# smarttrashcan.net
KiCad netlist of a schematic drawn in Altium Designer
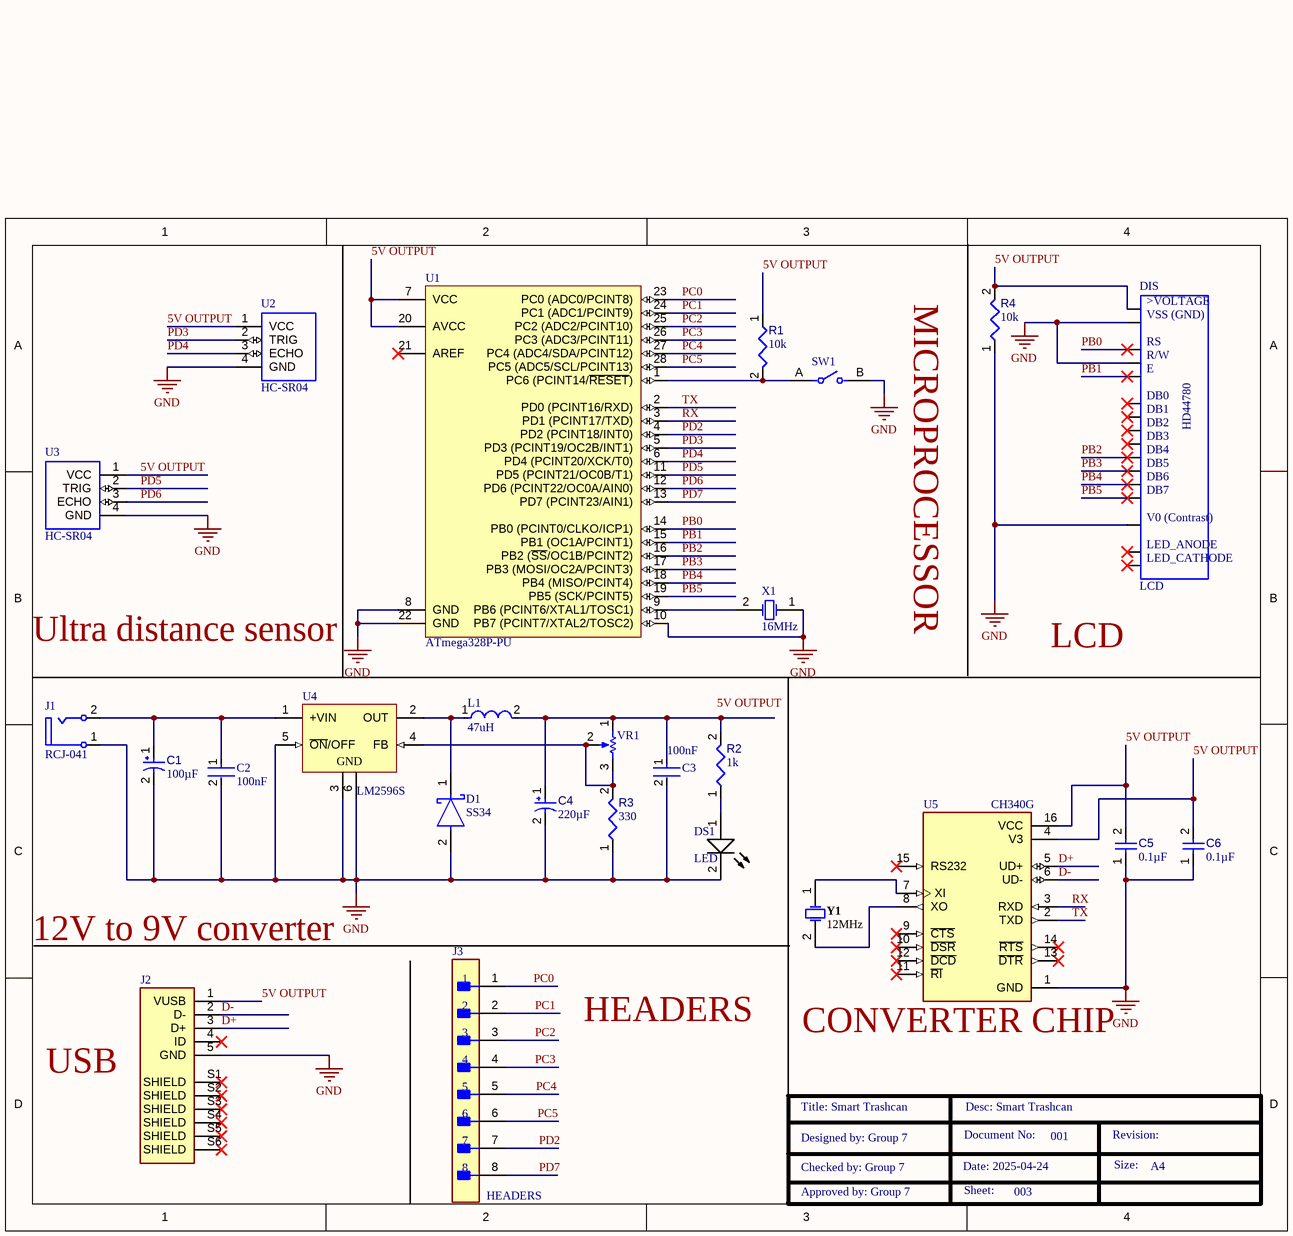
[diagram p0: smarttrashcan.SchDoc]

(export (version "E")
  (design (tool "Eeschema 10.0.6"))
  (components
    (comp (ref "C1")
      (value "100µF")
      (footprint "CAPPR65-500-1600X1000X1700")
      (description "Aluminum Electrolytic Capacitor, 100 uF, +/- 20%, 100 V, -40 to 85 degC, 2-Pin THD, RoHS, Bulk")
      (fields (field (name "MANUFACTURER") "Panasonic") (field (name "TOLERANCE") "20%"))
      (libsource (lib "Uy Pham") (part "CAP-P-2"))
    )
    (comp (ref "C2")
      (value "100nF")
      (footprint "FP-1812-L_4_5_0_3-W_3_2_0-IPC_C")
      (description "General Purpose Ceramic Capacitor, 1812, 100nF, 10%, X7R, 15%, 100V")
      (fields (field (name "TOLERANCE") "10%") (field (name "VOLTAGE") "100V"))
      (libsource (lib "Altium Content Vault") (part "02cd4be3c70576c341d710602a673aa"))
    )
    (comp (ref "C3")
      (value "100nF")
      (footprint "FP-1812-L_4_5_0_3-W_3_2_0-IPC_C")
      (description "General Purpose Ceramic Capacitor, 1812, 100nF, 10%, X7R, 15%, 100V")
      (fields (field (name "TOLERANCE") "10%") (field (name "VOLTAGE") "100V"))
      (libsource (lib "Altium Content Vault") (part "02cd4be3c70576c341d710602a673aa"))
    )
    (comp (ref "C4")
      (value "220µF")
      (footprint "CAPMP7344X31-T_V")
      (fields
        (field (name "TOLERANCE") "10%")
        (field (name "MANUFACTURER") "AVX Corporation")
        (field (name "Comment") "TPSD227K010R0150")
      )
      (libsource (lib "Uy Pham") (part "CAP-P-2"))
    )
    (comp (ref "C5")
      (value "0.1µF")
      (footprint "CAPC1005X56X25LL10T15")
      (description "Chip Capacitor, 0.1 uF, +/- 5%, 16 V, 0402 (1005 Metric)")
      (fields (field (name "TOLERANCE") "5%") (field (name "Comment") "Capacitor 0.1 uF +/- 5% 16 V 0402"))
      (libsource (lib "Uy Pham") (part "CAP-NP-2"))
    )
    (comp (ref "C6")
      (value "0.1µF")
      (footprint "CAPC1005X56X25LL10T15")
      (description "Chip Capacitor, 0.1 uF, +/- 5%, 16 V, 0402 (1005 Metric)")
      (fields (field (name "TOLERANCE") "5%") (field (name "Comment") "Capacitor 0.1 uF +/- 5% 16 V 0402"))
      (libsource (lib "Uy Pham") (part "CAP-NP-2"))
    )
    (comp (ref "D1")
      (value "SS34")
      (footprint "FP-95402-MFG")
      (description "DIODE SCHOTTKY 40V 3A DO214AB")
      (fields (field (name "MANUFACTURER") "Vishay") (field (name "MANUFACTURER PART NUMBER") "SS34-E3/57T"))
      (libsource (lib "Altium Content Vault") (part "1d6ec82d83fb6aee721767c19dac4b9"))
    )
    (comp (ref "DIS")
      (value "LCD")
      (footprint "16026-16X2")
      (fields (field (name "MP") "HD44780") (field (name "MF") "Lumex Opto/Components"))
      (libsource (lib "Uy Pham") (part "HD44780"))
    )
    (comp (ref "DS1")
      (value "LED")
      (footprint "EVRL-0402-2_V")
      (description "Chip LED, White, 5 V, 10 mA, 30 mW, -40 to 85 degC, 2-Pin SMD (0402), RoHS, Tape and Reel")
      (fields (field (name "POWER") "30mW") (field (name "MANUFACTURER") "Everlight Electronics"))
      (libsource (lib "Uy Pham") (part "LED-WHITE-AK-2"))
    )
    (comp (ref "J1")
      (value "RCJ-041")
      (footprint "CUI-RCJ-041_V")
      (description "Female RCJ Jack, 2 Position, Height 11.724 mm, Tail Length 4 mm, RoHS, Bulk")
      (fields (field (name "MANUFACTURER") "CUI Inc"))
      (libsource (lib "Uy Pham") (part "JACK-2CD2"))
    )
    (comp (ref "J2")
      (value "10118193-0001LF")
      (footprint "AMPHENOL_10118193-0001LF")
      (description "Right Angle Surface Mount Mount Female USB Connector 100 V ac 1.8A")
      (fields (field (name "MF") "Amphenol ICC"))
      (libsource (lib "Uy Pham") (part "10118193-0001LF"))
    )
    (comp (ref "J3")
      (value "HEADERS")
      (footprint "FP-22-11-2082-MFG")
      (description "CONN HEADER VERT 8POS 2.54MM")
      (libsource (lib "Altium Content Vault") (part "99ec2b232beb5d2356d4d77f6a047f0"))
    )
    (comp (ref "L1")
      (value "47uH")
      (footprint "FP-LB3225-2_5-0_2-IPC_B")
      (description "Commercial Inductors, Low DCR Series 47uH 3.3A 145mΩ 20%")
      (fields (field (name "TOLERANCE") "20%"))
      (libsource (lib "Altium Content Vault") (part "725321dda6339637d4d059423bc1c3c"))
    )
    (comp (ref "R1")
      (value "10k")
      (footprint "RESC0402(1005)_L")
      (description "10K 0.063W 1% 0402 (1005 Metric)  SMD")
      (fields (field (name "POWER") "63mW") (field (name "TOLERANCE") "1%"))
      (libsource (lib "Uy Pham") (part "10KR2F"))
    )
    (comp (ref "R2")
      (value "1k")
      (footprint "RESC0402(1005)_L")
      (description "1K 0.063W 5% 0402 (1005 Metric)  SMD")
      (fields (field (name "POWER") "63mW") (field (name "TOLERANCE") "5%"))
      (libsource (lib "Uy Pham") (part "1KR2J"))
    )
    (comp (ref "R3")
      (value "330")
      (footprint "RESC0402(1005)_L")
      (description "330R 0.063W 5% 0402 (1005 Metric)  SMD")
      (fields (field (name "TOLERANCE") "5%") (field (name "POWER") "63mW"))
      (libsource (lib "Uy Pham") (part "330R2J"))
    )
    (comp (ref "R4")
      (value "10k")
      (footprint "RESC0402(1005)_L")
      (description "10K 0.063W 1% 0402 (1005 Metric)  SMD")
      (fields (field (name "POWER") "63mW") (field (name "TOLERANCE") "1%"))
      (libsource (lib "Uy Pham") (part "10KR2F"))
    )
    (comp (ref "SW1")
      (value "EVQ11Y04K")
      (footprint "FP-EVQ11Y04K-MFG")
      (description "SWITCH TACTILE SPST-NO 0.02A 15V")
      (libsource (lib "Altium Content Vault") (part "2b0b2b19372efd94fa7681498149756"))
    )
    (comp (ref "U1")
      (value "ATmega328P-PU")
      (footprint "28P3")
      (libsource (lib "Altium Content Vault") (part "MC-8B-ATM48-IL28"))
    )
    (comp (ref "U2")
      (value "HC-SR04")
      (footprint "XCVR_HC-SR04")
      (description "Ultrasonic Sensor Module")
      (libsource (lib "Uy Pham") (part "HC-SR04"))
    )
    (comp (ref "U3")
      (value "HC-SR04")
      (footprint "XCVR_HC-SR04")
      (description "Ultrasonic Sensor Module")
      (libsource (lib "Uy Pham") (part "HC-SR04"))
    )
    (comp (ref "U4")
      (value "LM2596S")
      (footprint "KTT0005B_L")
      (fields (field (name "PARTNUMBER") "LM2596") (field (name "MANUFACTURER") "Texas Instruments"))
      (libsource (lib "Altium Content Vault") (part "TI-LM2596-TO-263-5"))
    )
    (comp (ref "U5")
      (value "CH340G")
      (footprint "SOIC127P600X180-16N")
      (description "USB Interface Integrated Circuit")
      (fields (field (name "MF") "WCH") (field (name "MP") "Ch340G"))
      (libsource (lib "Uy Pham") (part "CH340G"))
    )
    (comp (ref "VR1")
      (value "3296W-1-103LF")
      (footprint "BOUR-3296W")
      (fields
        (field (name "TOLERANCE") "10%")
        (field (name "POWER") "500mW")
        (field (name "MANUFACTURER") "Bourns")
      )
      (libsource (lib "Uy Pham") (part "RES-POT-3"))
    )
    (comp (ref "X1")
      (value "16MHz")
      (footprint "FOX-FOXSDLF160-20_V")
      (fields (field (name "TOLERANCE") "50ppm") (field (name "MANUFACTURER") "FOX Electronics"))
      (libsource (lib "Uy Pham") (part "XTAL_1-2-2"))
    )
    (comp (ref "Y1")
      (value "12MHz")
      (footprint "FOX-FOXSLF-2_V")
      (description "Resistance Weld Thru-Hole Crystal, 12 MHz, +/-30 ppm, 20 pF, -20 to 70 degC, 2-Pin THD, RoHS, Bulk")
      (fields (field (name "MANUFACTURER") "FOX Electronics") (field (name "TOLERANCE") "50ppm"))
      (libsource (lib "Uy Pham") (part "XTAL-1-2-2"))
    )
  )
  (nets
    (net (code "1") (name "/5V OUTPUT") (class "Default")
      (node (ref "C5") (pin "2") (pinfunction "2_2") (pintype "passive"))
      (node (ref "C6") (pin "2") (pinfunction "2_2") (pintype "passive"))
      (node (ref "DIS") (pin "P$2") (pinfunction "VDD_P$2") (pintype "bidirectional"))
      (node (ref "J2") (pin "1") (pinfunction "VUSB_1") (pintype "passive"))
      (node (ref "R1") (pin "1") (pinfunction "1_1") (pintype "passive"))
      (node (ref "R4") (pin "2") (pinfunction "2_2") (pintype "passive"))
      (node (ref "U1") (pin "20") (pinfunction "AVCC_20") (pintype "power_in"))
      (node (ref "U1") (pin "7") (pinfunction "VCC_7") (pintype "power_in"))
      (node (ref "U2") (pin "1") (pinfunction "VCC_1") (pintype "power_in"))
      (node (ref "U3") (pin "1") (pinfunction "VCC_1") (pintype "power_in"))
      (node (ref "U5") (pin "16") (pinfunction "VCC_16") (pintype "power_in"))
      (node (ref "U5") (pin "4") (pinfunction "V3_4") (pintype "power_in"))
    )
    (net (code "2") (name "/D+") (class "Default")
      (node (ref "J2") (pin "3") (pinfunction "D+_3") (pintype "passive"))
      (node (ref "U5") (pin "5") (pinfunction "UD+_5") (pintype "bidirectional"))
    )
    (net (code "3") (name "/D-") (class "Default")
      (node (ref "J2") (pin "2") (pinfunction "D-_2") (pintype "passive"))
      (node (ref "U5") (pin "6") (pinfunction "UD-_6") (pintype "bidirectional"))
    )
    (net (code "4") (name "/PB0") (class "Default")
      (node (ref "DIS") (pin "P$4") (pinfunction "RS_P$4") (pintype "bidirectional"))
      (node (ref "U1") (pin "14") (pinfunction "PB0_(PCINT0/CLKO/ICP1)_14") (pintype "bidirectional"))
    )
    (net (code "5") (name "/PB1") (class "Default")
      (node (ref "DIS") (pin "P$6") (pinfunction "E_P$6") (pintype "bidirectional"))
      (node (ref "U1") (pin "15") (pinfunction "PB1_(OC1A/PCINT1)_15") (pintype "bidirectional"))
    )
    (net (code "6") (name "/PB2") (class "Default")
      (node (ref "DIS") (pin "P$11") (pinfunction "DB4_P$11") (pintype "bidirectional"))
      (node (ref "U1") (pin "16") (pinfunction "PB2_(~{SS}/OC1B/PCINT2)_16") (pintype "bidirectional"))
    )
    (net (code "7") (name "/PB3") (class "Default")
      (node (ref "DIS") (pin "P$12") (pinfunction "DB5_P$12") (pintype "bidirectional"))
      (node (ref "U1") (pin "17") (pinfunction "PB3_(MOSI/OC2A/PCINT3)_17") (pintype "bidirectional"))
    )
    (net (code "8") (name "/PB4") (class "Default")
      (node (ref "DIS") (pin "P$13") (pinfunction "DB6_P$13") (pintype "bidirectional"))
      (node (ref "U1") (pin "18") (pinfunction "PB4_(MISO/PCINT4)_18") (pintype "bidirectional"))
    )
    (net (code "9") (name "/PB5") (class "Default")
      (node (ref "DIS") (pin "P$14") (pinfunction "DB7_P$14") (pintype "bidirectional"))
      (node (ref "U1") (pin "19") (pinfunction "PB5_(SCK/PCINT5)_19") (pintype "bidirectional"))
    )
    (net (code "10") (name "/PC0") (class "Default")
      (node (ref "J3") (pin "1") (pinfunction "1_1") (pintype "passive"))
      (node (ref "U1") (pin "23") (pinfunction "PC0_(ADC0/PCINT8)_23") (pintype "bidirectional"))
    )
    (net (code "11") (name "/PC1") (class "Default")
      (node (ref "J3") (pin "2") (pinfunction "2_2") (pintype "passive"))
      (node (ref "U1") (pin "24") (pinfunction "PC1_(ADC1/PCINT9)_24") (pintype "bidirectional"))
    )
    (net (code "12") (name "/PC2") (class "Default")
      (node (ref "J3") (pin "3") (pinfunction "3_3") (pintype "passive"))
      (node (ref "U1") (pin "25") (pinfunction "PC2_(ADC2/PCINT10)_25") (pintype "bidirectional"))
    )
    (net (code "13") (name "/PC3") (class "Default")
      (node (ref "J3") (pin "4") (pinfunction "4_4") (pintype "passive"))
      (node (ref "U1") (pin "26") (pinfunction "PC3_(ADC3/PCINT11)_26") (pintype "bidirectional"))
    )
    (net (code "14") (name "/PC4") (class "Default")
      (node (ref "J3") (pin "5") (pinfunction "5_5") (pintype "passive"))
      (node (ref "U1") (pin "27") (pinfunction "PC4_(ADC4/SDA/PCINT12)_27") (pintype "bidirectional"))
    )
    (net (code "15") (name "/PC5") (class "Default")
      (node (ref "J3") (pin "6") (pinfunction "6_6") (pintype "passive"))
      (node (ref "U1") (pin "28") (pinfunction "PC5_(ADC5/SCL/PCINT13)_28") (pintype "bidirectional"))
    )
    (net (code "16") (name "/PD2") (class "Default")
      (node (ref "J3") (pin "7") (pinfunction "7_7") (pintype "passive"))
      (node (ref "U1") (pin "4") (pinfunction "PD2_(PCINT18/INT0)_4") (pintype "bidirectional"))
    )
    (net (code "17") (name "/PD3") (class "Default")
      (node (ref "U1") (pin "5") (pinfunction "PD3_(PCINT19/OC2B/INT1)_5") (pintype "bidirectional"))
      (node (ref "U2") (pin "2") (pinfunction "TRIG_2") (pintype "bidirectional"))
    )
    (net (code "18") (name "/PD4") (class "Default")
      (node (ref "U1") (pin "6") (pinfunction "PD4_(PCINT20/XCK/T0)_6") (pintype "bidirectional"))
      (node (ref "U2") (pin "3") (pinfunction "ECHO_3") (pintype "bidirectional"))
    )
    (net (code "19") (name "/PD5") (class "Default")
      (node (ref "U1") (pin "11") (pinfunction "PD5_(PCINT21/OC0B/T1)_11") (pintype "bidirectional"))
      (node (ref "U3") (pin "2") (pinfunction "TRIG_2") (pintype "bidirectional"))
    )
    (net (code "20") (name "/PD6") (class "Default")
      (node (ref "U1") (pin "12") (pinfunction "PD6_(PCINT22/OC0A/AIN0)_12") (pintype "bidirectional"))
      (node (ref "U3") (pin "3") (pinfunction "ECHO_3") (pintype "bidirectional"))
    )
    (net (code "21") (name "/PD7") (class "Default")
      (node (ref "J3") (pin "8") (pinfunction "8_8") (pintype "passive"))
      (node (ref "U1") (pin "13") (pinfunction "PD7_(PCINT23/AIN1)_13") (pintype "bidirectional"))
    )
    (net (code "22") (name "/RX") (class "Default")
      (node (ref "U1") (pin "3") (pinfunction "PD1_(PCINT17/TXD)_3") (pintype "bidirectional"))
      (node (ref "U5") (pin "3") (pinfunction "RXD_3") (pintype "input"))
    )
    (net (code "23") (name "/TX") (class "Default")
      (node (ref "U1") (pin "2") (pinfunction "PD0_(PCINT16/RXD)_2") (pintype "bidirectional"))
      (node (ref "U5") (pin "2") (pinfunction "TXD_2") (pintype "output"))
    )
    (net (code "24") (name "GND") (class "Default")
      (node (ref "C1") (pin "2") (pinfunction "2_2") (pintype "passive"))
      (node (ref "C2") (pin "2") (pinfunction "2_2") (pintype "passive"))
      (node (ref "C3") (pin "2") (pinfunction "2_2") (pintype "passive"))
      (node (ref "C4") (pin "2") (pinfunction "2_2") (pintype "passive"))
      (node (ref "C5") (pin "1") (pinfunction "1_1") (pintype "passive"))
      (node (ref "C6") (pin "1") (pinfunction "1_1") (pintype "passive"))
      (node (ref "D1") (pin "2") (pinfunction "A_2") (pintype "passive"))
      (node (ref "DIS") (pin "P$1") (pinfunction "VSS_P$1") (pintype "bidirectional"))
      (node (ref "DIS") (pin "P$3") (pinfunction "CONTRAST_P$3") (pintype "bidirectional"))
      (node (ref "DIS") (pin "P$5") (pinfunction "R/W_P$5") (pintype "bidirectional"))
      (node (ref "DS1") (pin "2") (pinfunction "K_2") (pintype "passive"))
      (node (ref "J1") (pin "1") (pinfunction "1_1") (pintype "passive"))
      (node (ref "J2") (pin "5") (pinfunction "GND_5") (pintype "passive"))
      (node (ref "R3") (pin "1") (pinfunction "1_1") (pintype "passive"))
      (node (ref "R4") (pin "1") (pinfunction "1_1") (pintype "passive"))
      (node (ref "SW1") (pin "B") (pinfunction "B_B") (pintype "passive"))
      (node (ref "U1") (pin "10") (pinfunction "PB7_(PCINT7/XTAL2/TOSC2)_10") (pintype "bidirectional"))
      (node (ref "U1") (pin "22") (pinfunction "GND_22") (pintype "power_in"))
      (node (ref "U1") (pin "8") (pinfunction "GND_8") (pintype "power_in"))
      (node (ref "U2") (pin "4") (pinfunction "GND_4") (pintype "power_in"))
      (node (ref "U3") (pin "4") (pinfunction "GND_4") (pintype "power_in"))
      (node (ref "U4") (pin "3") (pinfunction "GND_3") (pintype "power_in"))
      (node (ref "U4") (pin "5") (pinfunction "~{ON}/OFF_5") (pintype "input"))
      (node (ref "U4") (pin "6") (pinfunction "GND_6") (pintype "power_in"))
      (node (ref "U5") (pin "1") (pinfunction "GND_1") (pintype "power_in"))
      (node (ref "X1") (pin "1") (pinfunction "X1_1") (pintype "passive"))
    )
    (net (code "25") (name "Net-(D1-C)") (class "Default")
      (node (ref "D1") (pin "1") (pinfunction "C_1") (pintype "passive"))
      (node (ref "L1") (pin "1") (pinfunction "1_1") (pintype "passive"))
      (node (ref "U4") (pin "2") (pinfunction "OUT_2") (pintype "power_in"))
    )
    (net (code "26") (name "Net-(DS1-A)") (class "Default")
      (node (ref "DS1") (pin "1") (pinfunction "A_1") (pintype "passive"))
      (node (ref "R2") (pin "1") (pinfunction "1_1") (pintype "passive"))
    )
    (net (code "27") (name "Net-(U1-PB6_(PCINT6{slash}XTAL1{slash}TOSC1))") (class "Default")
      (node (ref "U1") (pin "9") (pinfunction "PB6_(PCINT6/XTAL1/TOSC1)_9") (pintype "bidirectional"))
      (node (ref "X1") (pin "2") (pinfunction "X2_2") (pintype "passive"))
    )
    (net (code "28") (name "Net-(U1-PC6_(PCINT14{slash}~{RESET}))") (class "Default")
      (node (ref "R1") (pin "2") (pinfunction "2_2") (pintype "passive"))
      (node (ref "SW1") (pin "A") (pinfunction "A_A") (pintype "passive"))
      (node (ref "U1") (pin "1") (pinfunction "PC6_(PCINT14/~{RESET})_1") (pintype "bidirectional"))
    )
    (net (code "29") (name "Net-(U4-+VIN)") (class "Default")
      (node (ref "C1") (pin "1") (pinfunction "1_1") (pintype "passive"))
      (node (ref "C2") (pin "1") (pinfunction "1_1") (pintype "passive"))
      (node (ref "J1") (pin "2") (pinfunction "2_2") (pintype "passive"))
      (node (ref "U4") (pin "1") (pinfunction "+VIN_1") (pintype "power_in"))
    )
    (net (code "30") (name "Net-(U4-FB)") (class "Default")
      (node (ref "R3") (pin "2") (pinfunction "2_2") (pintype "passive"))
      (node (ref "U4") (pin "4") (pinfunction "FB_4") (pintype "input"))
      (node (ref "VR1") (pin "2") (pinfunction "S_2") (pintype "passive"))
      (node (ref "VR1") (pin "3") (pinfunction "CW_3") (pintype "passive"))
    )
    (net (code "31") (name "Net-(U5-XI)") (class "Default")
      (node (ref "U5") (pin "7") (pinfunction "XI_7") (pintype "input"))
      (node (ref "Y1") (pin "1") (pinfunction "1_1") (pintype "passive"))
    )
    (net (code "32") (name "Net-(U5-XO)") (class "Default")
      (node (ref "U5") (pin "8") (pinfunction "XO_8") (pintype "output"))
      (node (ref "Y1") (pin "2") (pinfunction "2_2") (pintype "passive"))
    )
    (net (code "33") (name "Net-(VR1-CCW)") (class "Default")
      (node (ref "C3") (pin "1") (pinfunction "1_1") (pintype "passive"))
      (node (ref "C4") (pin "1") (pinfunction "1_1") (pintype "passive"))
      (node (ref "L1") (pin "2") (pinfunction "2_2") (pintype "passive"))
      (node (ref "R2") (pin "2") (pinfunction "2_2") (pintype "passive"))
      (node (ref "VR1") (pin "1") (pinfunction "CCW_1") (pintype "passive"))
    )
    (net (code "34") (name "unconnected-(DIS-DB0-PadP$7)") (class "Default")
      (node (ref "DIS") (pin "P$7") (pinfunction "DB0_P$7") (pintype "bidirectional+no_connect"))
    )
    (net (code "35") (name "unconnected-(DIS-DB1-PadP$8)") (class "Default")
      (node (ref "DIS") (pin "P$8") (pinfunction "DB1_P$8") (pintype "bidirectional+no_connect"))
    )
    (net (code "36") (name "unconnected-(DIS-DB2-PadP$9)") (class "Default")
      (node (ref "DIS") (pin "P$9") (pinfunction "DB2_P$9") (pintype "bidirectional+no_connect"))
    )
    (net (code "37") (name "unconnected-(DIS-DB3-PadP$10)") (class "Default")
      (node (ref "DIS") (pin "P$10") (pinfunction "DB3_P$10") (pintype "bidirectional+no_connect"))
    )
    (net (code "38") (name "unconnected-(DIS-LED_A-PadP$15)") (class "Default")
      (node (ref "DIS") (pin "P$15") (pinfunction "LED_A_P$15") (pintype "bidirectional+no_connect"))
    )
    (net (code "39") (name "unconnected-(DIS-LED_C-PadP$16)") (class "Default")
      (node (ref "DIS") (pin "P$16") (pinfunction "LED_C_P$16") (pintype "bidirectional+no_connect"))
    )
    (net (code "40") (name "unconnected-(J2-ID-Pad4)") (class "Default")
      (node (ref "J2") (pin "4") (pinfunction "ID_4") (pintype "passive+no_connect"))
    )
    (net (code "41") (name "unconnected-(J2-SHIELD-PadS1)") (class "Default")
      (node (ref "J2") (pin "S1") (pinfunction "SHIELD_S1") (pintype "passive+no_connect"))
    )
    (net (code "42") (name "unconnected-(J2-SHIELD-PadS2)") (class "Default")
      (node (ref "J2") (pin "S2") (pinfunction "SHIELD_S2") (pintype "passive+no_connect"))
    )
    (net (code "43") (name "unconnected-(J2-SHIELD-PadS3)") (class "Default")
      (node (ref "J2") (pin "S3") (pinfunction "SHIELD_S3") (pintype "passive+no_connect"))
    )
    (net (code "44") (name "unconnected-(J2-SHIELD-PadS4)") (class "Default")
      (node (ref "J2") (pin "S4") (pinfunction "SHIELD_S4") (pintype "passive+no_connect"))
    )
    (net (code "45") (name "unconnected-(J2-SHIELD-PadS5)") (class "Default")
      (node (ref "J2") (pin "S5") (pinfunction "SHIELD_S5") (pintype "passive+no_connect"))
    )
    (net (code "46") (name "unconnected-(J2-SHIELD-PadS6)") (class "Default")
      (node (ref "J2") (pin "S6") (pinfunction "SHIELD_S6") (pintype "passive+no_connect"))
    )
    (net (code "47") (name "unconnected-(U1-AREF-Pad21)") (class "Default")
      (node (ref "U1") (pin "21") (pinfunction "AREF_21") (pintype "power_in+no_connect"))
    )
    (net (code "48") (name "unconnected-(U5-RS232-Pad15)") (class "Default")
      (node (ref "U5") (pin "15") (pinfunction "RS232_15") (pintype "input+no_connect"))
    )
    (net (code "49") (name "unconnected-(U5-~{CTS}-Pad9)") (class "Default")
      (node (ref "U5") (pin "9") (pinfunction "~{CTS}_9") (pintype "input+no_connect"))
    )
    (net (code "50") (name "unconnected-(U5-~{DCD}-Pad12)") (class "Default")
      (node (ref "U5") (pin "12") (pinfunction "~{DCD}_12") (pintype "input+no_connect"))
    )
    (net (code "51") (name "unconnected-(U5-~{DSR}-Pad10)") (class "Default")
      (node (ref "U5") (pin "10") (pinfunction "~{DSR}_10") (pintype "input+no_connect"))
    )
    (net (code "52") (name "unconnected-(U5-~{DTR}-Pad13)") (class "Default")
      (node (ref "U5") (pin "13") (pinfunction "~{DTR}_13") (pintype "output+no_connect"))
    )
    (net (code "53") (name "unconnected-(U5-~{RI}-Pad11)") (class "Default")
      (node (ref "U5") (pin "11") (pinfunction "~{RI}_11") (pintype "input+no_connect"))
    )
    (net (code "54") (name "unconnected-(U5-~{RTS}-Pad14)") (class "Default")
      (node (ref "U5") (pin "14") (pinfunction "~{RTS}_14") (pintype "output+no_connect"))
    )
  )
)
